# 001-Main.net
KiCad netlist of a schematic drawn in Altium Designer
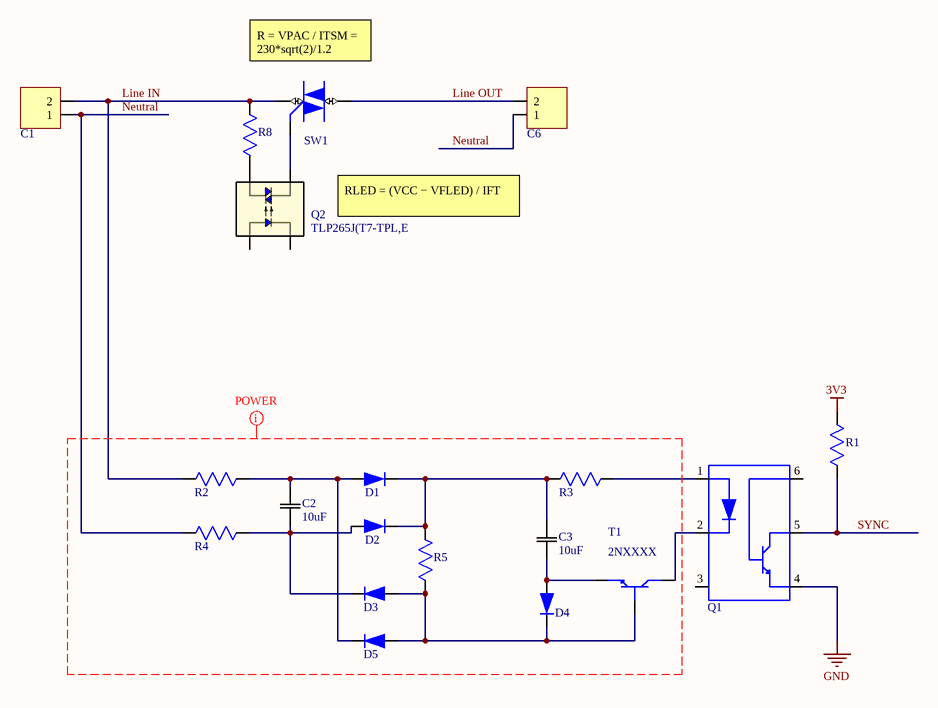
[diagram p0: 001-Main.SchDoc]

(export (version "E")
  (design (tool "Eeschema 10.0.6"))
  (components
    (comp (ref "C1")
      (value "DG128-5.0-02P-14")
      (footprint "DG128-5.0-02P-14")
      (libsource (lib "Connectors") (part "Connector 2P 5.0mm"))
    )
    (comp (ref "C2")
      (value "10uF")
      (footprint "CAP 0603/1608")
      (description "CAP 10uF Ceramic 0603 capacitor")
      (libsource (lib "MyLibrary") (part "CL10A106KQ8NNNC"))
    )
    (comp (ref "C3")
      (value "10uF")
      (footprint "CAP 0603/1608")
      (description "CAP 10uF Ceramic 0603 capacitor")
      (libsource (lib "MyLibrary") (part "CL10A106KQ8NNNC"))
    )
    (comp (ref "C6")
      (value "DG128-5.0-02P-14")
      (footprint "DG128-5.0-02P-14")
      (libsource (lib "") (part "Connector 2P 5.0mm_1"))
    )
    (comp (ref "D1")
      (value "MMSD4148T1G")
      (footprint "SOD-123")
      (description "DIODE")
      (fields (field (name "COPYRIGHT") "Copyright (C) 2025 Ultra Librarian. All rights reserved."))
      (libsource (lib "MyLibrary") (part "MMSD4148T1G"))
    )
    (comp (ref "D2")
      (value "MMSD4148T1G")
      (footprint "SOD-123")
      (description "DIODE")
      (fields (field (name "COPYRIGHT") "Copyright (C) 2025 Ultra Librarian. All rights reserved."))
      (libsource (lib "MyLibrary") (part "MMSD4148T1G"))
    )
    (comp (ref "D3")
      (value "MMSD4148T1G")
      (footprint "SOD-123")
      (description "DIODE")
      (fields (field (name "COPYRIGHT") "Copyright (C) 2025 Ultra Librarian. All rights reserved."))
      (libsource (lib "MyLibrary") (part "MMSD4148T1G"))
    )
    (comp (ref "D4")
      (value "MMSD4148T1G")
      (footprint "SOD-123")
      (description "DIODE")
      (fields (field (name "COPYRIGHT") "Copyright (C) 2025 Ultra Librarian. All rights reserved."))
      (libsource (lib "MyLibrary") (part "MMSD4148T1G"))
    )
    (comp (ref "D5")
      (value "MMSD4148T1G")
      (footprint "SOD-123")
      (description "DIODE")
      (fields (field (name "COPYRIGHT") "Copyright (C) 2025 Ultra Librarian. All rights reserved."))
      (libsource (lib "MyLibrary") (part "MMSD4148T1G"))
    )
    (comp (ref "Q1")
      (value "4N35")
      (footprint "DIP6-2.54")
      (description "Optoisolator Transistor with Base Output 5000Vrms 1 Channel 6-DIP")
      (fields (field (name "MF") "Vishay"))
      (libsource (lib "MyLibrary") (part "4N35"))
    )
    (comp (ref "Q2")
      (value "TLP265J(T7-TPL,E")
      (footprint "4pin SO6_TOS")
      (description "No Description Available")
      (fields (field (name "COPYRIGHT") "Copyright (C) 2025 Ultra Librarian. All rights reserved."))
      (libsource (lib "MyLibrary") (part "TLP265JT7-TPL,E"))
    )
    (comp (ref "R1")
      (value "CRCW06031K00FKEA")
      (footprint "CAP 0603/1608")
      (description "D11/CRCW0603 100 1K 1% ET1 e3")
      (fields (field (name "COPYRIGHT") "Copyright (C) 2025 Ultra Librarian. All rights reserved."))
      (libsource (lib "MyLibrary") (part "CRCW06031K00FKEA"))
    )
    (comp (ref "R2")
      (value "CRCW06031K00FKEA")
      (footprint "CAP 0603/1608")
      (description "D11/CRCW0603 100 1K 1% ET1 e3")
      (fields (field (name "COPYRIGHT") "Copyright (C) 2025 Ultra Librarian. All rights reserved."))
      (libsource (lib "MyLibrary") (part "CRCW06031K00FKEA"))
    )
    (comp (ref "R3")
      (value "CRCW06031K00FKEA")
      (footprint "CAP 0603/1608")
      (description "D11/CRCW0603 100 1K 1% ET1 e3")
      (fields (field (name "COPYRIGHT") "Copyright (C) 2025 Ultra Librarian. All rights reserved."))
      (libsource (lib "MyLibrary") (part "CRCW06031K00FKEA"))
    )
    (comp (ref "R4")
      (value "CRCW06031K00FKEA")
      (footprint "CAP 0603/1608")
      (description "D11/CRCW0603 100 1K 1% ET1 e3")
      (fields (field (name "COPYRIGHT") "Copyright (C) 2025 Ultra Librarian. All rights reserved."))
      (libsource (lib "MyLibrary") (part "CRCW06031K00FKEA"))
    )
    (comp (ref "R5")
      (value "CRCW06031K00FKEA")
      (footprint "CAP 0603/1608")
      (description "D11/CRCW0603 100 1K 1% ET1 e3")
      (fields (field (name "COPYRIGHT") "Copyright (C) 2025 Ultra Librarian. All rights reserved."))
      (libsource (lib "MyLibrary") (part "CRCW06031K00FKEA"))
    )
    (comp (ref "R8")
      (value "CRCW06031K00FKEA")
      (footprint "CAP 0603/1608")
      (description "D11/CRCW0603 100 1K 1% ET1 e3")
      (fields (field (name "COPYRIGHT") "Copyright (C) 2025 Ultra Librarian. All rights reserved."))
      (libsource (lib "MyLibrary") (part "CRCW06031K00FKEA"))
    )
    (comp (ref "SW1")
      (value "T810T-8G-TR")
      (footprint "D2PAK")
      (description "8A 800V 150&#176;C D&#178;PAK Logic Level T-Series Triac")
      (fields (field (name "COPYRIGHT") "Copyright (C) 2025 Ultra Librarian. All rights reserved."))
      (libsource (lib "MyLibrary") (part "T810T-8G-TR"))
    )
    (comp (ref "T1") (value "2NXXXX") (footprint "TO-92") (libsource (lib "MyLibrary") (part "2NXXXX")))
  )
  (nets
    (net (code "1") (name "/Line IN") (class "Default")
      (node (ref "C1") (pin "2") (pinfunction "2_2") (pintype "passive"))
      (node (ref "R2") (pin "1") (pinfunction "1_1") (pintype "passive"))
      (node (ref "R8") (pin "2") (pinfunction "2_2") (pintype "passive"))
      (node (ref "SW1") (pin "1") (pinfunction "A1_1") (pintype "bidirectional"))
    )
    (net (code "2") (name "/Line OUT") (class "Default")
      (node (ref "C6") (pin "2") (pinfunction "2_2") (pintype "passive"))
      (node (ref "SW1") (pin "2") (pinfunction "A2_2") (pintype "bidirectional"))
    )
    (net (code "3") (name "/Neutral") (class "Default")
      (node (ref "C1") (pin "1") (pinfunction "1_1") (pintype "passive"))
      (node (ref "C6") (pin "1") (pinfunction "1_1") (pintype "passive"))
      (node (ref "R4") (pin "1") (pinfunction "1_1") (pintype "passive"))
    )
    (net (code "4") (name "/SYNC") (class "Default")
      (node (ref "Q1") (pin "5") (pinfunction "COLLECTOR_5") (pintype "bidirectional"))
      (node (ref "R1") (pin "1") (pinfunction "1_1") (pintype "passive"))
    )
    (net (code "5") (name "3V3") (class "Default")
      (node (ref "R1") (pin "2") (pinfunction "2_2") (pintype "passive"))
    )
    (net (code "6") (name "GND") (class "Default")
      (node (ref "Q1") (pin "4") (pinfunction "EMITER_4") (pintype "bidirectional"))
    )
    (net (code "7") (name "Net-(D1-A)") (class "Default")
      (node (ref "C3") (pin "2") (pinfunction "2_2") (pintype "passive"))
      (node (ref "D1") (pin "2") (pinfunction "A_2") (pintype "passive"))
      (node (ref "D2") (pin "2") (pinfunction "A_2") (pintype "passive"))
      (node (ref "R3") (pin "1") (pinfunction "1_1") (pintype "passive"))
      (node (ref "R5") (pin "1") (pinfunction "1_1") (pintype "passive"))
    )
    (net (code "8") (name "Net-(D1-K)") (class "Default")
      (node (ref "C2") (pin "2") (pinfunction "2_2") (pintype "passive"))
      (node (ref "D1") (pin "1") (pinfunction "K_1") (pintype "passive"))
      (node (ref "D5") (pin "2") (pinfunction "A_2") (pintype "passive"))
      (node (ref "R2") (pin "2") (pinfunction "2_2") (pintype "passive"))
    )
    (net (code "9") (name "Net-(D2-K)") (class "Default")
      (node (ref "C2") (pin "1") (pinfunction "1_1") (pintype "passive"))
      (node (ref "D2") (pin "1") (pinfunction "K_1") (pintype "passive"))
      (node (ref "D3") (pin "2") (pinfunction "A_2") (pintype "passive"))
      (node (ref "R4") (pin "2") (pinfunction "2_2") (pintype "passive"))
    )
    (net (code "10") (name "Net-(D3-K)") (class "Default")
      (node (ref "D3") (pin "1") (pinfunction "K_1") (pintype "passive"))
      (node (ref "D4") (pin "2") (pinfunction "A_2") (pintype "passive"))
      (node (ref "D5") (pin "1") (pinfunction "K_1") (pintype "passive"))
      (node (ref "R5") (pin "2") (pinfunction "2_2") (pintype "passive"))
      (node (ref "T1") (pin "1") (pinfunction "B_1") (pintype "passive"))
    )
    (net (code "11") (name "Net-(D4-K)") (class "Default")
      (node (ref "C3") (pin "1") (pinfunction "1_1") (pintype "passive"))
      (node (ref "D4") (pin "1") (pinfunction "K_1") (pintype "passive"))
      (node (ref "T1") (pin "3") (pinfunction "E_3") (pintype "passive"))
    )
    (net (code "12") (name "Net-(Q1-ANODE)") (class "Default")
      (node (ref "Q1") (pin "1") (pinfunction "ANODE_1") (pintype "bidirectional"))
      (node (ref "R3") (pin "2") (pinfunction "2_2") (pintype "passive"))
    )
    (net (code "13") (name "Net-(Q1-CATHODE)") (class "Default")
      (node (ref "Q1") (pin "2") (pinfunction "CATHODE_2") (pintype "bidirectional"))
      (node (ref "T1") (pin "2") (pinfunction "C_2") (pintype "passive"))
    )
    (net (code "14") (name "Net-(Q2-Pad6)") (class "Default")
      (node (ref "Q2") (pin "6") (pinfunction "6_6") (pintype "passive"))
      (node (ref "R8") (pin "1") (pinfunction "1_1") (pintype "passive"))
    )
    (net (code "15") (name "Net-(SW1-G)") (class "Default")
      (node (ref "Q2") (pin "4") (pinfunction "4_4") (pintype "passive"))
      (node (ref "SW1") (pin "3") (pinfunction "G_3") (pintype "passive"))
    )
    (net (code "16") (name "unconnected-(Q1-BASE-Pad6)") (class "Default")
      (node (ref "Q1") (pin "6") (pinfunction "BASE_6") (pintype "bidirectional"))
    )
    (net (code "17") (name "unconnected-(Q1-NC-Pad3)") (class "Default")
      (node (ref "Q1") (pin "3") (pinfunction "NC_3") (pintype "bidirectional"))
    )
    (net (code "18") (name "unconnected-(Q2-Pad1)") (class "Default")
      (node (ref "Q2") (pin "1") (pinfunction "1_1") (pintype "passive"))
    )
    (net (code "19") (name "unconnected-(Q2-Pad3)") (class "Default")
      (node (ref "Q2") (pin "3") (pinfunction "3_3") (pintype "passive"))
    )
  )
)
